# power-supply.net
KiCad netlist of a schematic drawn in EAGLE
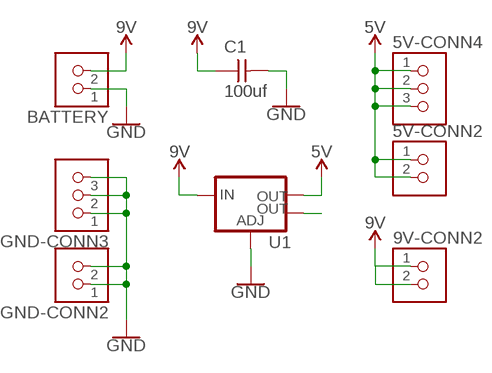
[diagram p0: schematic, sheet 1]

(export (version "E")
  (design (tool "Eeschema 10.0.6"))
  (components
    (comp (ref "5V-CONN2")
      (value "TERM-1X02-FABLAB")
      (footprint "eagle-import:ED555DS-2DS")
      (libsource (lib "eagle-import") (part "TERM-1X02-FABLAB"))
    )
    (comp (ref "5V-CONN4")
      (value "TERM-1X03'-FABLAB'")
      (footprint "eagle-import:ED555DS-3DS")
      (libsource (lib "eagle-import") (part "TERM-1X03'-FABLAB'"))
    )
    (comp (ref "9V-CONN2")
      (value "TERM-1X02-FABLAB")
      (footprint "eagle-import:ED555DS-2DS")
      (libsource (lib "eagle-import") (part "TERM-1X02-FABLAB"))
    )
    (comp (ref "BATTERY")
      (value "TERM-1X02-FABLAB")
      (footprint "eagle-import:ED555DS-2DS")
      (libsource (lib "eagle-import") (part "TERM-1X02-FABLAB"))
    )
    (comp (ref "C1")
      (value "100uf")
      (footprint "eagle-import:C1206FAB")
      (libsource (lib "eagle-import") (part "CAP-UNPOLARIZEDFAB"))
    )
    (comp (ref "GND-CONN2")
      (value "TERM-1X02-FABLAB")
      (footprint "eagle-import:ED555DS-2DS")
      (libsource (lib "eagle-import") (part "TERM-1X02-FABLAB"))
    )
    (comp (ref "GND-CONN3")
      (value "TERM-1X03'-FABLAB'")
      (footprint "eagle-import:ED555DS-3DS")
      (libsource (lib "eagle-import") (part "TERM-1X03'-FABLAB'"))
    )
    (comp (ref "U1")
      (value "V_REG_LM1117SOT223")
      (footprint "eagle-import:SOT223")
      (libsource (lib "eagle-import") (part "V_REG_LM1117SOT223"))
    )
  )
  (nets
    (net (code "1") (name "5V") (class "Default")
      (node (ref "5V-CONN2") (pin "1") (pinfunction "1_1") (pintype "passive"))
      (node (ref "5V-CONN2") (pin "2") (pinfunction "2_2") (pintype "passive"))
      (node (ref "5V-CONN4") (pin "1") (pinfunction "1_1") (pintype "passive"))
      (node (ref "5V-CONN4") (pin "2") (pinfunction "2_2") (pintype "passive"))
      (node (ref "5V-CONN4") (pin "3") (pinfunction "3_3") (pintype "passive"))
      (node (ref "U1") (pin "2") (pinfunction "OUT_2") (pintype "output"))
    )
    (net (code "2") (name "9V") (class "Default")
      (node (ref "9V-CONN2") (pin "1") (pinfunction "1_1") (pintype "passive"))
      (node (ref "9V-CONN2") (pin "2") (pinfunction "2_2") (pintype "passive"))
      (node (ref "BATTERY") (pin "2") (pinfunction "2_2") (pintype "passive"))
      (node (ref "C1") (pin "1") (pinfunction "1_1") (pintype "passive"))
      (node (ref "U1") (pin "3") (pinfunction "IN_3") (pintype "input"))
    )
    (net (code "3") (name "GND") (class "Default")
      (node (ref "BATTERY") (pin "1") (pinfunction "1_1") (pintype "passive"))
      (node (ref "C1") (pin "2") (pinfunction "2_2") (pintype "passive"))
      (node (ref "GND-CONN2") (pin "1") (pinfunction "1_1") (pintype "passive"))
      (node (ref "GND-CONN2") (pin "2") (pinfunction "2_2") (pintype "passive"))
      (node (ref "GND-CONN3") (pin "1") (pinfunction "1_1") (pintype "passive"))
      (node (ref "GND-CONN3") (pin "2") (pinfunction "2_2") (pintype "passive"))
      (node (ref "GND-CONN3") (pin "3") (pinfunction "3_3") (pintype "passive"))
      (node (ref "U1") (pin "1") (pinfunction "ADJ_1") (pintype "input"))
    )
    (net (code "4") (name "unconnected-(U1-OUT-Pad4)") (class "Default")
      (node (ref "U1") (pin "4") (pinfunction "OUT_4") (pintype "output"))
    )
  )
)
